# PlungerV3R7A_15cm_x_2_5cm.net
KiCad netlist of a schematic drawn in EAGLE
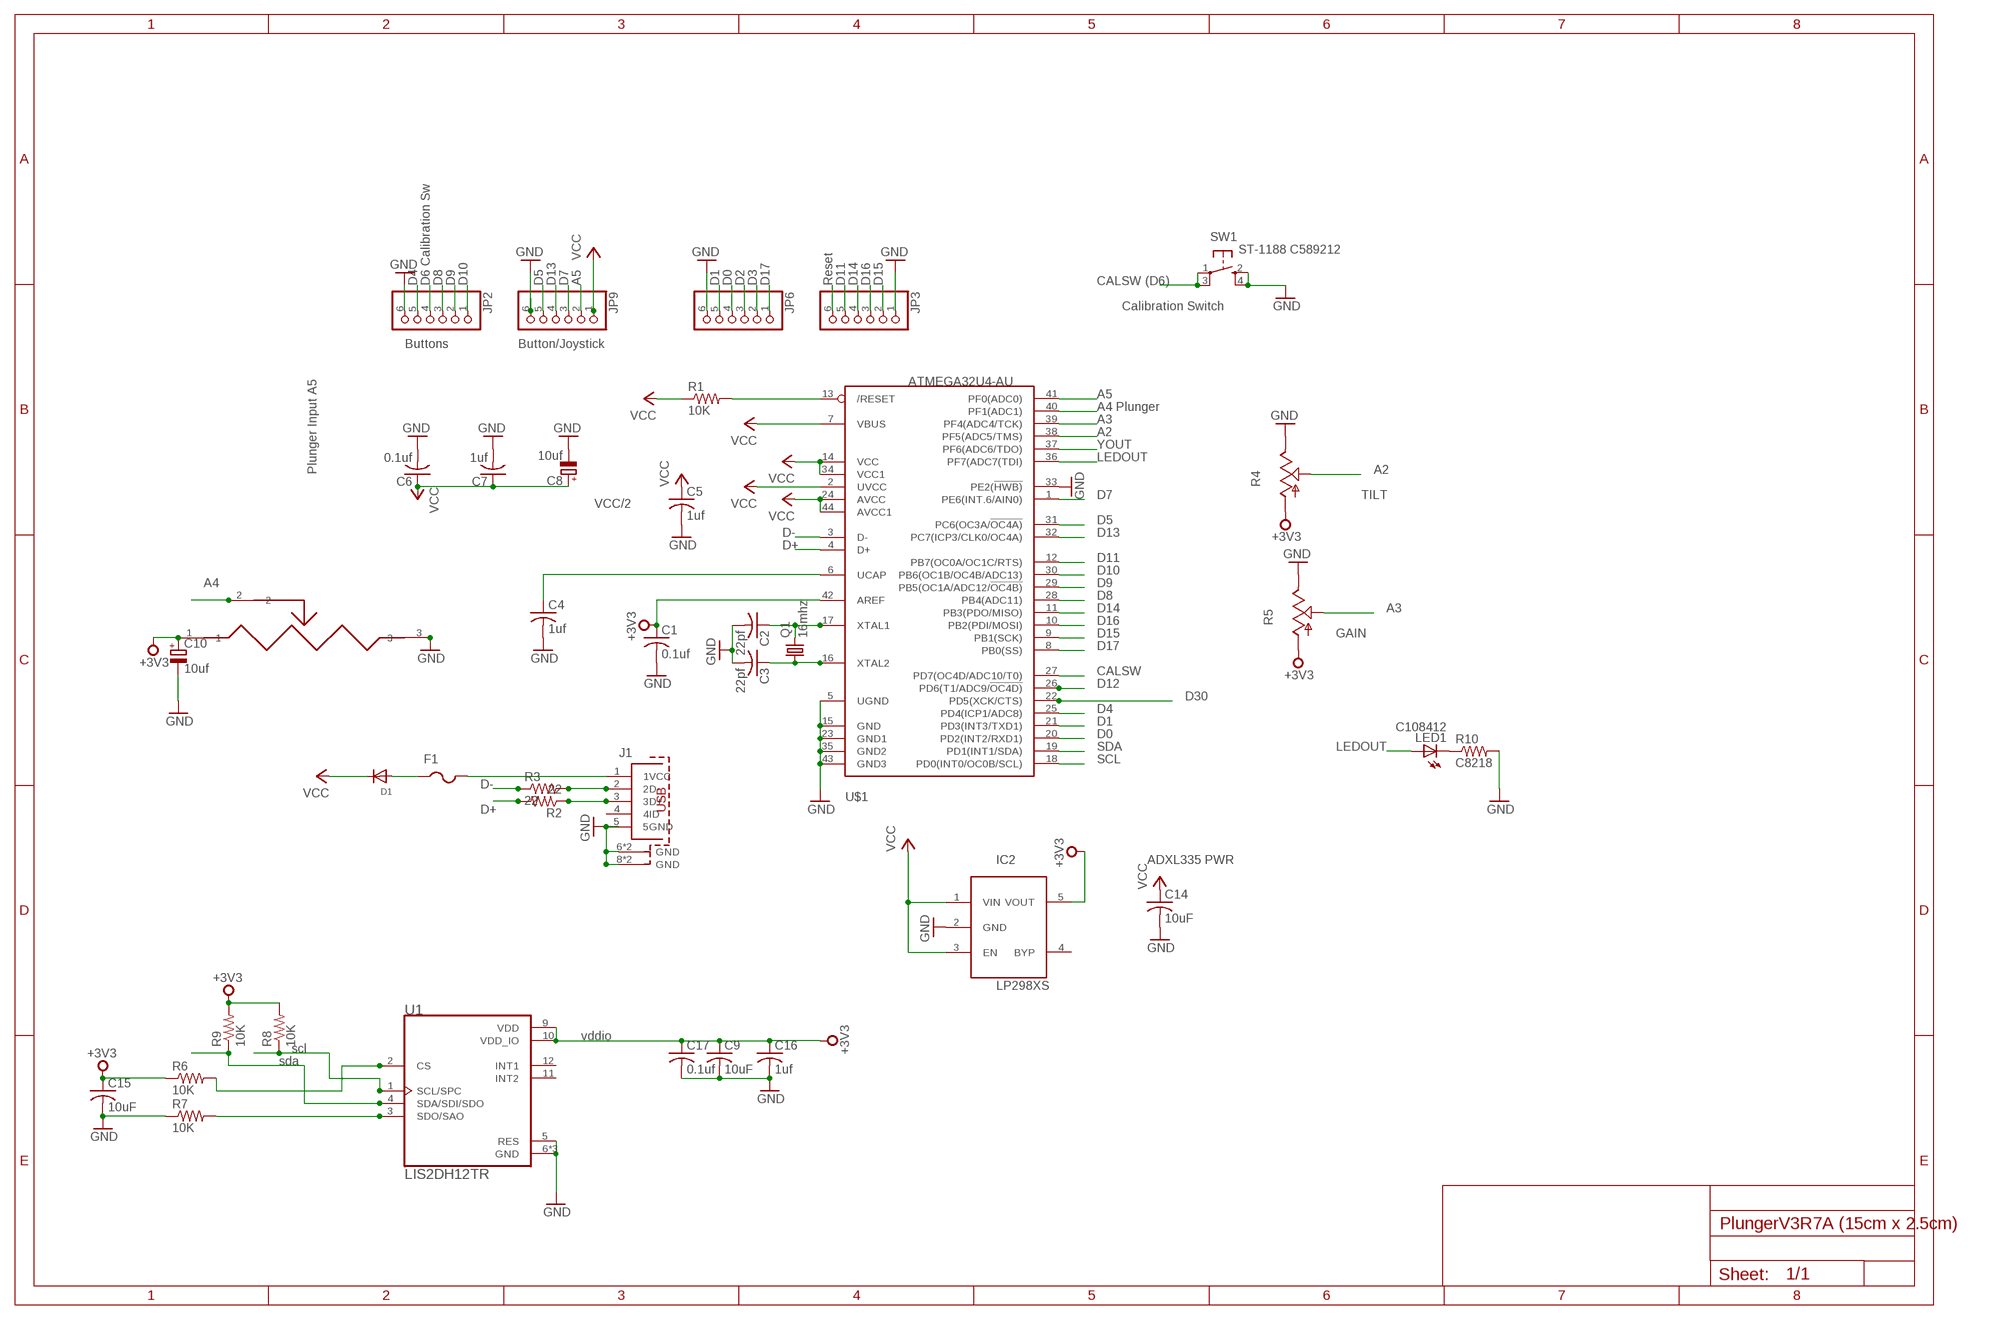
[diagram p0: schematic, sheet 1]

(export (version "E")
  (design (tool "Eeschema 10.0.6"))
  (components
    (comp (ref "C1")
      (value "0.1uf")
      (footprint "eagle-import:C0603")
      (libsource (lib "eagle-import") (part "C-USC0603"))
    )
    (comp (ref "C2")
      (value "22pf")
      (footprint "eagle-import:C0603")
      (libsource (lib "eagle-import") (part "C-USC0603"))
    )
    (comp (ref "C3")
      (value "22pf")
      (footprint "eagle-import:C0603")
      (libsource (lib "eagle-import") (part "C-USC0603"))
    )
    (comp (ref "C4")
      (value "1uf")
      (footprint "eagle-import:C0603")
      (libsource (lib "eagle-import") (part "resistor_C-USC0603"))
    )
    (comp (ref "C5")
      (value "1uf")
      (footprint "eagle-import:C0603")
      (libsource (lib "eagle-import") (part "resistor_C-USC0603"))
    )
    (comp (ref "C6")
      (value "0.1uf")
      (footprint "eagle-import:C0603")
      (libsource (lib "eagle-import") (part "C-USC0603"))
    )
    (comp (ref "C7")
      (value "1uf")
      (footprint "eagle-import:C0603")
      (libsource (lib "eagle-import") (part "resistor_C-USC0603"))
    )
    (comp (ref "C8")
      (value "10uf")
      (footprint "eagle-import:A_3216-18W")
      (libsource (lib "eagle-import") (part "CPOL-EUA/3216-18W"))
    )
    (comp (ref "C9")
      (value "10uF")
      (footprint "eagle-import:C0805K")
      (libsource (lib "eagle-import") (part "C-USC0805K"))
    )
    (comp (ref "C10")
      (value "10uf")
      (footprint "eagle-import:A_3216-18W")
      (libsource (lib "eagle-import") (part "CPOL-EUA/3216-18W"))
    )
    (comp (ref "C14")
      (value "10uF")
      (footprint "eagle-import:C0805K")
      (libsource (lib "eagle-import") (part "C-USC0805K"))
    )
    (comp (ref "C15")
      (value "10uF")
      (footprint "eagle-import:C0805K")
      (libsource (lib "eagle-import") (part "C-USC0805K"))
    )
    (comp (ref "C16")
      (value "1uf")
      (footprint "eagle-import:C0603")
      (libsource (lib "eagle-import") (part "resistor_C-USC0603"))
    )
    (comp (ref "C17")
      (value "0.1uf")
      (footprint "eagle-import:C0603")
      (libsource (lib "eagle-import") (part "C-USC0603"))
    )
    (comp (ref "D1")
      (value "DIODESMA")
      (footprint "eagle-import:SMADIODE")
      (libsource (lib "eagle-import") (part "DIODESMA"))
    )
    (comp (ref "F1")
      (value "PTCFUSE-1812")
      (footprint "eagle-import:1812")
      (libsource (lib "eagle-import") (part "PTCFUSE-1812"))
    )
    (comp (ref "IC2")
      (value "LP298XS")
      (footprint "eagle-import:SOT23-5L")
      (libsource (lib "eagle-import") (part "LP298XS"))
    )
    (comp (ref "J1")
      (value "651005136521")
      (footprint "eagle-import:651005136521")
      (libsource (lib "eagle-import") (part "651005136521"))
    )
    (comp (ref "JP2")
      (value "PINHD-1X6B")
      (footprint "eagle-import:1X06-BIG")
      (libsource (lib "eagle-import") (part "PINHD-1X6B"))
    )
    (comp (ref "JP3")
      (value "PINHD-1X6B")
      (footprint "eagle-import:1X06-BIG")
      (libsource (lib "eagle-import") (part "PINHD-1X6B"))
    )
    (comp (ref "JP6")
      (value "PINHD-1X6B")
      (footprint "eagle-import:1X06-BIG")
      (libsource (lib "eagle-import") (part "PINHD-1X6B"))
    )
    (comp (ref "JP9")
      (value "PINHD-1X6B")
      (footprint "eagle-import:1X06-BIG")
      (libsource (lib "eagle-import") (part "PINHD-1X6B"))
    )
    (comp (ref "LED1")
      (value "C108412")
      (footprint "eagle-import:CHIP-LED0805")
      (libsource (lib "eagle-import") (part "LEDCHIP-LED0805"))
    )
    (comp (ref "Q1")
      (value "16mhz")
      (footprint "eagle-import:CTS406")
      (libsource (lib "eagle-import") (part "CRYSTALCTS406"))
    )
    (comp (ref "R1")
      (value "10K")
      (footprint "eagle-import:M0805")
      (libsource (lib "eagle-import") (part "R-US_M0805"))
    )
    (comp (ref "R2")
      (value "22")
      (footprint "eagle-import:R0603")
      (libsource (lib "eagle-import") (part "R-US_R0603"))
    )
    (comp (ref "R3")
      (value "22")
      (footprint "eagle-import:R0603")
      (libsource (lib "eagle-import") (part "R-US_R0603"))
    )
    (comp (ref "R4")
      (value "TRIM_US-B25P")
      (footprint "eagle-import:B25P")
      (libsource (lib "eagle-import") (part "TRIM_US-B25P"))
    )
    (comp (ref "R5")
      (value "TRIM_US-B25P")
      (footprint "eagle-import:B25P")
      (libsource (lib "eagle-import") (part "TRIM_US-B25P"))
    )
    (comp (ref "R6")
      (value "10K")
      (footprint "eagle-import:R0805")
      (libsource (lib "eagle-import") (part "R-US_R0805"))
    )
    (comp (ref "R7")
      (value "10K")
      (footprint "eagle-import:R0603")
      (libsource (lib "eagle-import") (part "R-US_R0603"))
    )
    (comp (ref "R8")
      (value "10K")
      (footprint "eagle-import:R0603")
      (libsource (lib "eagle-import") (part "R-US_R0603"))
    )
    (comp (ref "R9")
      (value "10K")
      (footprint "eagle-import:R0603")
      (libsource (lib "eagle-import") (part "R-US_R0603"))
    )
    (comp (ref "R10")
      (value "C8218")
      (footprint "eagle-import:M0805")
      (libsource (lib "eagle-import") (part "R-US_M0805"))
    )
    (comp (ref "SW1")
      (value "ST-1188 C589212")
      (footprint "eagle-import:KMR2")
      (libsource (lib "eagle-import") (part "SPST_TACT-KMR2"))
    )
    (comp (ref "U$1")
      (value "ATMEGA32U4-AU")
      (footprint "eagle-import:TQFP44")
      (libsource (lib "eagle-import") (part "ATMEGA32U4-AU"))
    )
    (comp (ref "U$7")
      (value "PS100POTENTIOMETER")
      (footprint "eagle-import:PS100")
      (libsource (lib "eagle-import") (part "PS100POTENTIOMETER"))
    )
    (comp (ref "U1")
      (value "LIS2DH12TR")
      (footprint "eagle-import:PQFN50P200X200100-12N")
      (description "Accelerometer X, Y, Z Axis ±2g, 4g, 8g, 16g 0.5Hz ~ 672Hz 12-LGA (2x2)")
      (fields
        (field (name "MF") "STMicroelectronics")
        (field (name "MP") "LIS2DH12TR")
        (field (name "PURCHASE-URL") "https://pricing.snapeda.com/search/part/LIS2DH12TR/?ref=eda")
      )
      (libsource (lib "eagle-import") (part "LIS2DH12TR"))
    )
  )
  (nets
    (net (code "1") (name "+3V3") (class "Default")
      (node (ref "C1") (pin "1") (pinfunction "1_1") (pintype "passive"))
      (node (ref "C10") (pin "+") (pinfunction "+_+") (pintype "passive"))
      (node (ref "C15") (pin "1") (pinfunction "1_1") (pintype "passive"))
      (node (ref "C16") (pin "1") (pinfunction "1_1") (pintype "passive"))
      (node (ref "C17") (pin "1") (pinfunction "1_1") (pintype "passive"))
      (node (ref "C9") (pin "1") (pinfunction "1_1") (pintype "passive"))
      (node (ref "IC2") (pin "5") (pinfunction "VOUT_5") (pintype "bidirectional"))
      (node (ref "R4") (pin "A") (pinfunction "A_A") (pintype "passive"))
      (node (ref "R5") (pin "A") (pinfunction "A_A") (pintype "passive"))
      (node (ref "R6") (pin "1") (pinfunction "1_1") (pintype "passive"))
      (node (ref "R8") (pin "2") (pinfunction "2_2") (pintype "passive"))
      (node (ref "R9") (pin "2") (pinfunction "2_2") (pintype "passive"))
      (node (ref "U$1") (pin "42") (pinfunction "AREF_42") (pintype "bidirectional"))
      (node (ref "U$7") (pin "1") (pinfunction "1_1") (pintype "bidirectional"))
      (node (ref "U1") (pin "10") (pinfunction "VDD_IO_10") (pintype "power_in"))
      (node (ref "U1") (pin "9") (pinfunction "VDD_9") (pintype "power_in"))
    )
    (net (code "2") (name "/A2") (class "Default")
      (node (ref "R4") (pin "S") (pinfunction "S_S") (pintype "passive"))
      (node (ref "U$1") (pin "38") (pinfunction "PF5(ADC5/TMS)_38") (pintype "bidirectional"))
    )
    (net (code "3") (name "/A3") (class "Default")
      (node (ref "R5") (pin "S") (pinfunction "S_S") (pintype "passive"))
      (node (ref "U$1") (pin "39") (pinfunction "PF4(ADC4/TCK)_39") (pintype "bidirectional"))
    )
    (net (code "4") (name "/A4") (class "Default")
      (node (ref "U$1") (pin "40") (pinfunction "PF1(ADC1)_40") (pintype "bidirectional"))
      (node (ref "U$7") (pin "2") (pinfunction "2_2") (pintype "bidirectional"))
    )
    (net (code "5") (name "/A5") (class "Default")
      (node (ref "JP9") (pin "2") (pinfunction "2_2") (pintype "passive"))
      (node (ref "U$1") (pin "41") (pinfunction "PF0(ADC0)_41") (pintype "bidirectional"))
    )
    (net (code "6") (name "/CALSW") (class "Default")
      (node (ref "JP2") (pin "4") (pinfunction "4_4") (pintype "passive"))
      (node (ref "SW1") (pin "1") (pinfunction "P_1") (pintype "passive"))
      (node (ref "SW1") (pin "3") (pinfunction "P1_3") (pintype "passive"))
      (node (ref "U$1") (pin "27") (pinfunction "PD7(OC4D/ADC10/T0)_27") (pintype "bidirectional"))
    )
    (net (code "7") (name "/D+") (class "Default")
      (node (ref "R2") (pin "2") (pinfunction "2_2") (pintype "passive"))
      (node (ref "U$1") (pin "4") (pinfunction "D+_4") (pintype "bidirectional"))
    )
    (net (code "8") (name "/D-") (class "Default")
      (node (ref "R3") (pin "1") (pinfunction "1_1") (pintype "passive"))
      (node (ref "U$1") (pin "3") (pinfunction "D-_3") (pintype "bidirectional"))
    )
    (net (code "9") (name "/D0") (class "Default")
      (node (ref "JP6") (pin "4") (pinfunction "4_4") (pintype "passive"))
      (node (ref "U$1") (pin "20") (pinfunction "PD2(INT2/RXD1)_20") (pintype "bidirectional"))
    )
    (net (code "10") (name "/D1") (class "Default")
      (node (ref "JP6") (pin "5") (pinfunction "5_5") (pintype "passive"))
      (node (ref "U$1") (pin "21") (pinfunction "PD3(INT3/TXD1)_21") (pintype "bidirectional"))
    )
    (net (code "11") (name "/D4") (class "Default")
      (node (ref "JP2") (pin "5") (pinfunction "5_5") (pintype "passive"))
      (node (ref "U$1") (pin "25") (pinfunction "PD4(ICP1/ADC8)_25") (pintype "bidirectional"))
    )
    (net (code "12") (name "/D5") (class "Default")
      (node (ref "JP9") (pin "5") (pinfunction "5_5") (pintype "passive"))
      (node (ref "U$1") (pin "31") (pinfunction "PC6(OC3A/~{OC4A})_31") (pintype "bidirectional"))
    )
    (net (code "13") (name "/D7") (class "Default")
      (node (ref "JP9") (pin "3") (pinfunction "3_3") (pintype "passive"))
      (node (ref "U$1") (pin "1") (pinfunction "PE6(INT.6/AIN0)_1") (pintype "bidirectional"))
    )
    (net (code "14") (name "/D8") (class "Default")
      (node (ref "JP2") (pin "3") (pinfunction "3_3") (pintype "passive"))
      (node (ref "U$1") (pin "28") (pinfunction "PB4(ADC11)_28") (pintype "bidirectional"))
    )
    (net (code "15") (name "/D9") (class "Default")
      (node (ref "JP2") (pin "2") (pinfunction "2_2") (pintype "passive"))
      (node (ref "U$1") (pin "29") (pinfunction "PB5(OC1A/ADC12/~{OC4B})_29") (pintype "bidirectional"))
    )
    (net (code "16") (name "/D10") (class "Default")
      (node (ref "JP2") (pin "1") (pinfunction "1_1") (pintype "passive"))
      (node (ref "U$1") (pin "30") (pinfunction "PB6(OC1B/OC4B/ADC13)_30") (pintype "bidirectional"))
    )
    (net (code "17") (name "/D11") (class "Default")
      (node (ref "JP3") (pin "5") (pinfunction "5_5") (pintype "passive"))
      (node (ref "U$1") (pin "12") (pinfunction "PB7(OC0A/OC1C/RTS)_12") (pintype "bidirectional"))
    )
    (net (code "18") (name "/D13") (class "Default")
      (node (ref "JP9") (pin "4") (pinfunction "4_4") (pintype "passive"))
      (node (ref "U$1") (pin "32") (pinfunction "PC7(ICP3/CLK0/OC4A)_32") (pintype "bidirectional"))
    )
    (net (code "19") (name "/D14") (class "Default")
      (node (ref "JP3") (pin "4") (pinfunction "4_4") (pintype "passive"))
      (node (ref "U$1") (pin "11") (pinfunction "PB3(PDO/MISO)_11") (pintype "bidirectional"))
    )
    (net (code "20") (name "/D15") (class "Default")
      (node (ref "JP3") (pin "2") (pinfunction "2_2") (pintype "passive"))
      (node (ref "U$1") (pin "9") (pinfunction "PB1(SCK)_9") (pintype "bidirectional"))
    )
    (net (code "21") (name "/D16") (class "Default")
      (node (ref "JP3") (pin "3") (pinfunction "3_3") (pintype "passive"))
      (node (ref "U$1") (pin "10") (pinfunction "PB2(PDI/MOSI)_10") (pintype "bidirectional"))
    )
    (net (code "22") (name "/D17") (class "Default")
      (node (ref "JP6") (pin "1") (pinfunction "1_1") (pintype "passive"))
      (node (ref "U$1") (pin "8") (pinfunction "PB0(SS)_8") (pintype "bidirectional"))
    )
    (net (code "23") (name "/LEDOUT") (class "Default")
      (node (ref "LED1") (pin "A") (pinfunction "A_A") (pintype "passive"))
      (node (ref "U$1") (pin "36") (pinfunction "PF7(ADC7(TDI)_36") (pintype "bidirectional"))
    )
    (net (code "24") (name "/RST") (class "Default")
      (node (ref "JP3") (pin "6") (pinfunction "6_6") (pintype "passive"))
      (node (ref "R1") (pin "2") (pinfunction "2_2") (pintype "passive"))
      (node (ref "U$1") (pin "13") (pinfunction "/RESET_13") (pintype "bidirectional"))
    )
    (net (code "25") (name "/SCL") (class "Default")
      (node (ref "JP6") (pin "2") (pinfunction "2_2") (pintype "passive"))
      (node (ref "R8") (pin "1") (pinfunction "1_1") (pintype "passive"))
      (node (ref "U$1") (pin "18") (pinfunction "PD0(INT0/OC0B/SCL)_18") (pintype "bidirectional"))
      (node (ref "U1") (pin "1") (pinfunction "SCL/SPC_1") (pintype "bidirectional"))
    )
    (net (code "26") (name "/SDA") (class "Default")
      (node (ref "JP6") (pin "3") (pinfunction "3_3") (pintype "passive"))
      (node (ref "R9") (pin "1") (pinfunction "1_1") (pintype "passive"))
      (node (ref "U$1") (pin "19") (pinfunction "PD1(INT1/SDA)_19") (pintype "bidirectional"))
      (node (ref "U1") (pin "4") (pinfunction "SDA/SDI/SDO_4") (pintype "bidirectional"))
    )
    (net (code "27") (name "GND") (class "Default")
      (node (ref "C1") (pin "2") (pinfunction "2_2") (pintype "passive"))
      (node (ref "C10") (pin "-") (pinfunction "-_-") (pintype "passive"))
      (node (ref "C14") (pin "2") (pinfunction "2_2") (pintype "passive"))
      (node (ref "C15") (pin "2") (pinfunction "2_2") (pintype "passive"))
      (node (ref "C16") (pin "2") (pinfunction "2_2") (pintype "passive"))
      (node (ref "C17") (pin "2") (pinfunction "2_2") (pintype "passive"))
      (node (ref "C2") (pin "2") (pinfunction "2_2") (pintype "passive"))
      (node (ref "C3") (pin "2") (pinfunction "2_2") (pintype "passive"))
      (node (ref "C4") (pin "2") (pinfunction "2_2") (pintype "passive"))
      (node (ref "C5") (pin "2") (pinfunction "2_2") (pintype "passive"))
      (node (ref "C6") (pin "2") (pinfunction "2_2") (pintype "passive"))
      (node (ref "C7") (pin "2") (pinfunction "2_2") (pintype "passive"))
      (node (ref "C8") (pin "-") (pinfunction "-_-") (pintype "passive"))
      (node (ref "C9") (pin "2") (pinfunction "2_2") (pintype "passive"))
      (node (ref "IC2") (pin "2") (pinfunction "GND_2") (pintype "bidirectional"))
      (node (ref "J1") (pin "5") (pinfunction "5GND_5") (pintype "passive"))
      (node (ref "J1") (pin "6") (pinfunction "GND_6") (pintype "bidirectional"))
      (node (ref "J1") (pin "7") (pinfunction "GND_7") (pintype "bidirectional"))
      (node (ref "J1") (pin "8") (pinfunction "GND_8") (pintype "bidirectional"))
      (node (ref "J1") (pin "9") (pinfunction "GND_9") (pintype "bidirectional"))
      (node (ref "JP2") (pin "6") (pinfunction "6_6") (pintype "passive"))
      (node (ref "JP3") (pin "1") (pinfunction "1_1") (pintype "passive"))
      (node (ref "JP6") (pin "6") (pinfunction "6_6") (pintype "passive"))
      (node (ref "JP9") (pin "6") (pinfunction "6_6") (pintype "passive"))
      (node (ref "R10") (pin "2") (pinfunction "2_2") (pintype "passive"))
      (node (ref "R4") (pin "E") (pinfunction "E_E") (pintype "passive"))
      (node (ref "R5") (pin "E") (pinfunction "E_E") (pintype "passive"))
      (node (ref "R7") (pin "1") (pinfunction "1_1") (pintype "passive"))
      (node (ref "SW1") (pin "2") (pinfunction "S_2") (pintype "passive"))
      (node (ref "SW1") (pin "4") (pinfunction "S1_4") (pintype "passive"))
      (node (ref "U$1") (pin "15") (pinfunction "GND_15") (pintype "bidirectional"))
      (node (ref "U$1") (pin "23") (pinfunction "GND1_23") (pintype "bidirectional"))
      (node (ref "U$1") (pin "33") (pinfunction "PE2(~{HWB})_33") (pintype "bidirectional"))
      (node (ref "U$1") (pin "35") (pinfunction "GND2_35") (pintype "bidirectional"))
      (node (ref "U$1") (pin "43") (pinfunction "GND3_43") (pintype "bidirectional"))
      (node (ref "U$1") (pin "5") (pinfunction "UGND_5") (pintype "bidirectional"))
      (node (ref "U$7") (pin "3") (pinfunction "3_3") (pintype "bidirectional"))
      (node (ref "U1") (pin "5") (pinfunction "RES_5") (pintype "power_in"))
      (node (ref "U1") (pin "6") (pinfunction "GND_6") (pintype "power_in"))
      (node (ref "U1") (pin "7") (pinfunction "GND_7") (pintype "power_in"))
      (node (ref "U1") (pin "8") (pinfunction "GND_8") (pintype "power_in"))
    )
    (net (code "28") (name "Net-(D1-PadA)") (class "Default")
      (node (ref "D1") (pin "A") (pinfunction "A_A") (pintype "passive"))
      (node (ref "F1") (pin "1") (pinfunction "1_1") (pintype "passive"))
    )
    (net (code "29") (name "Net-(J1-1VCC)") (class "Default")
      (node (ref "F1") (pin "2") (pinfunction "2_2") (pintype "passive"))
      (node (ref "J1") (pin "1") (pinfunction "1VCC_1") (pintype "passive"))
    )
    (net (code "30") (name "Net-(J1-2D-)") (class "Default")
      (node (ref "J1") (pin "2") (pinfunction "2D-_2") (pintype "passive"))
      (node (ref "R3") (pin "2") (pinfunction "2_2") (pintype "passive"))
    )
    (net (code "31") (name "Net-(J1-3D+)") (class "Default")
      (node (ref "J1") (pin "3") (pinfunction "3D+_3") (pintype "passive"))
      (node (ref "R2") (pin "1") (pinfunction "1_1") (pintype "passive"))
    )
    (net (code "32") (name "Net-(LED1-PadC)") (class "Default")
      (node (ref "LED1") (pin "C") (pinfunction "C_C") (pintype "passive"))
      (node (ref "R10") (pin "1") (pinfunction "1_1") (pintype "passive"))
    )
    (net (code "33") (name "Net-(Q1-2)") (class "Default")
      (node (ref "C2") (pin "1") (pinfunction "1_1") (pintype "passive"))
      (node (ref "Q1") (pin "3") (pinfunction "2_3") (pintype "passive"))
      (node (ref "U$1") (pin "17") (pinfunction "XTAL1_17") (pintype "bidirectional"))
    )
    (net (code "34") (name "Net-(U$1-UCAP)") (class "Default")
      (node (ref "C4") (pin "1") (pinfunction "1_1") (pintype "passive"))
      (node (ref "U$1") (pin "6") (pinfunction "UCAP_6") (pintype "bidirectional"))
    )
    (net (code "35") (name "Net-(U$1-XTAL2)") (class "Default")
      (node (ref "C3") (pin "1") (pinfunction "1_1") (pintype "passive"))
      (node (ref "Q1") (pin "1") (pinfunction "1_1") (pintype "passive"))
      (node (ref "U$1") (pin "16") (pinfunction "XTAL2_16") (pintype "bidirectional"))
    )
    (net (code "36") (name "Net-(U1-CS)") (class "Default")
      (node (ref "R6") (pin "2") (pinfunction "2_2") (pintype "passive"))
      (node (ref "U1") (pin "2") (pinfunction "CS_2") (pintype "input"))
    )
    (net (code "37") (name "Net-(U1-SDO{slash}SAO)") (class "Default")
      (node (ref "R7") (pin "2") (pinfunction "2_2") (pintype "passive"))
      (node (ref "U1") (pin "3") (pinfunction "SDO/SAO_3") (pintype "bidirectional"))
    )
    (net (code "38") (name "VCC") (class "Default")
      (node (ref "C14") (pin "1") (pinfunction "1_1") (pintype "passive"))
      (node (ref "C5") (pin "1") (pinfunction "1_1") (pintype "passive"))
      (node (ref "C6") (pin "1") (pinfunction "1_1") (pintype "passive"))
      (node (ref "C7") (pin "1") (pinfunction "1_1") (pintype "passive"))
      (node (ref "C8") (pin "+") (pinfunction "+_+") (pintype "passive"))
      (node (ref "D1") (pin "C") (pinfunction "C_C") (pintype "passive"))
      (node (ref "IC2") (pin "1") (pinfunction "VIN_1") (pintype "bidirectional"))
      (node (ref "IC2") (pin "3") (pinfunction "EN_3") (pintype "bidirectional"))
      (node (ref "JP9") (pin "1") (pinfunction "1_1") (pintype "passive"))
      (node (ref "R1") (pin "1") (pinfunction "1_1") (pintype "passive"))
      (node (ref "U$1") (pin "14") (pinfunction "VCC_14") (pintype "bidirectional"))
      (node (ref "U$1") (pin "2") (pinfunction "UVCC_2") (pintype "bidirectional"))
      (node (ref "U$1") (pin "24") (pinfunction "AVCC_24") (pintype "bidirectional"))
      (node (ref "U$1") (pin "34") (pinfunction "VCC1_34") (pintype "bidirectional"))
      (node (ref "U$1") (pin "44") (pinfunction "AVCC1_44") (pintype "bidirectional"))
      (node (ref "U$1") (pin "7") (pinfunction "VBUS_7") (pintype "bidirectional"))
    )
    (net (code "39") (name "unconnected-(IC2-BYP-Pad4)") (class "Default")
      (node (ref "IC2") (pin "4") (pinfunction "BYP_4") (pintype "bidirectional"))
    )
    (net (code "40") (name "unconnected-(J1-4ID-Pad4)") (class "Default")
      (node (ref "J1") (pin "4") (pinfunction "4ID_4") (pintype "passive"))
    )
    (net (code "41") (name "unconnected-(U$1-PD5(XCK{slash}CTS)-Pad22)") (class "Default")
      (node (ref "U$1") (pin "22") (pinfunction "PD5(XCK/CTS)_22") (pintype "bidirectional"))
    )
    (net (code "42") (name "unconnected-(U$1-PD6(T1{slash}ADC9{slash}~{OC4D})-Pad26)") (class "Default")
      (node (ref "U$1") (pin "26") (pinfunction "PD6(T1/ADC9/~{OC4D})_26") (pintype "bidirectional"))
    )
    (net (code "43") (name "unconnected-(U$1-PF6(ADC6{slash}TDO)-Pad37)") (class "Default")
      (node (ref "U$1") (pin "37") (pinfunction "PF6(ADC6/TDO)_37") (pintype "bidirectional"))
    )
    (net (code "44") (name "unconnected-(U1-INT1-Pad12)") (class "Default")
      (node (ref "U1") (pin "12") (pinfunction "INT1_12") (pintype "output"))
    )
    (net (code "45") (name "unconnected-(U1-INT2-Pad11)") (class "Default")
      (node (ref "U1") (pin "11") (pinfunction "INT2_11") (pintype "output"))
    )
  )
)
